# pcb_telemetria.net
KiCad netlist of a schematic drawn in EAGLE
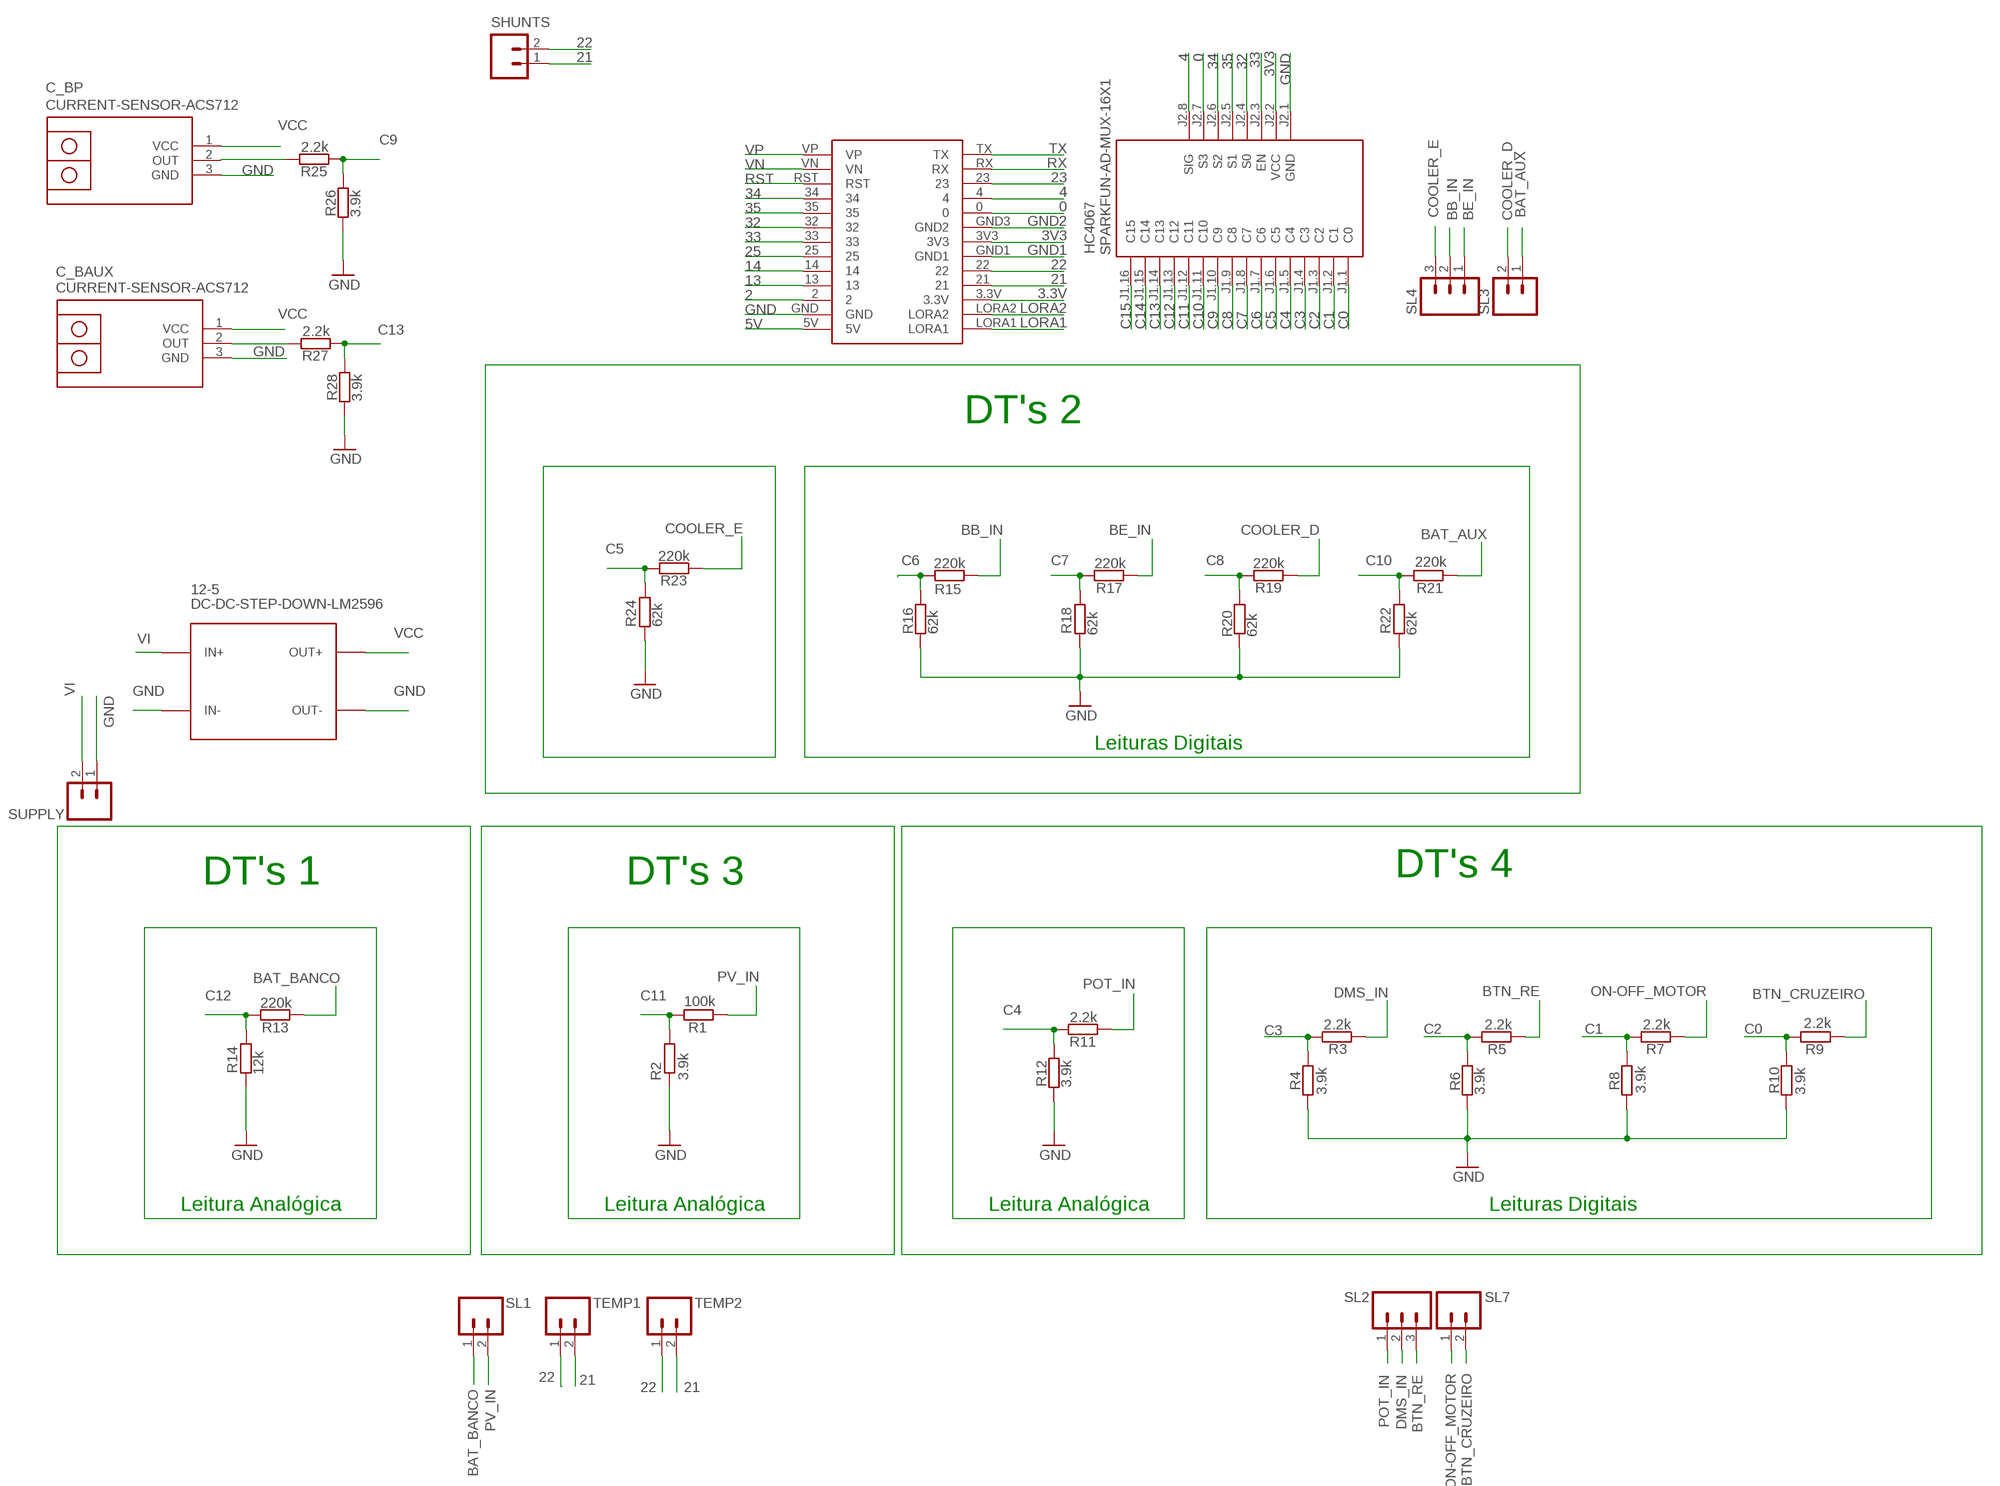
[diagram p0: schematic, sheet 1]

(export (version "E")
  (design (tool "Eeschema 10.0.6"))
  (components
    (comp (ref "12-5")
      (value "DC-DC-STEP-DOWN-LM2596")
      (footprint "eagle-import:DC-DC-STEP-DOWN-LM2596")
      (libsource (lib "eagle-import") (part "DC-DC-STEP-DOWN-LM2596"))
    )
    (comp (ref "C_BAUX")
      (value "CURRENT-SENSOR-ACS712")
      (footprint "eagle-import:CURRENT-SENSOR-ACS712")
      (libsource (lib "eagle-import") (part "CURRENT-SENSOR-ACS712"))
    )
    (comp (ref "C_BP")
      (value "CURRENT-SENSOR-ACS712")
      (footprint "eagle-import:CURRENT-SENSOR-ACS712")
      (libsource (lib "eagle-import") (part "CURRENT-SENSOR-ACS712"))
    )
    (comp (ref "HC4067")
      (value "SPARKFUN-AD-MUX-16X1")
      (footprint "eagle-import:SPARKFUN-AD-MUX-16X1")
      (libsource (lib "eagle-import") (part "SPARKFUN-AD-MUX-16X1"))
    )
    (comp (ref "R1")
      (value "100k")
      (footprint "eagle-import:0204_7")
      (libsource (lib "eagle-import") (part "R-EU_0204/7"))
    )
    (comp (ref "R2")
      (value "3.9k")
      (footprint "eagle-import:0204_7")
      (libsource (lib "eagle-import") (part "R-EU_0204/7"))
    )
    (comp (ref "R3")
      (value "2.2k")
      (footprint "eagle-import:0204_7")
      (libsource (lib "eagle-import") (part "R-EU_0204/7"))
    )
    (comp (ref "R4")
      (value "3.9k")
      (footprint "eagle-import:0204_7")
      (libsource (lib "eagle-import") (part "R-EU_0204/7"))
    )
    (comp (ref "R5")
      (value "2.2k")
      (footprint "eagle-import:0204_7")
      (libsource (lib "eagle-import") (part "R-EU_0204/7"))
    )
    (comp (ref "R6")
      (value "3.9k")
      (footprint "eagle-import:0204_7")
      (libsource (lib "eagle-import") (part "R-EU_0204/7"))
    )
    (comp (ref "R7")
      (value "2.2k")
      (footprint "eagle-import:0204_7")
      (libsource (lib "eagle-import") (part "R-EU_0204/7"))
    )
    (comp (ref "R8")
      (value "3.9k")
      (footprint "eagle-import:0204_7")
      (libsource (lib "eagle-import") (part "R-EU_0204/7"))
    )
    (comp (ref "R9")
      (value "2.2k")
      (footprint "eagle-import:0204_7")
      (libsource (lib "eagle-import") (part "R-EU_0204/7"))
    )
    (comp (ref "R10")
      (value "3.9k")
      (footprint "eagle-import:0204_7")
      (libsource (lib "eagle-import") (part "R-EU_0204/7"))
    )
    (comp (ref "R11")
      (value "2.2k")
      (footprint "eagle-import:0204_7")
      (libsource (lib "eagle-import") (part "R-EU_0204/7"))
    )
    (comp (ref "R12")
      (value "3.9k")
      (footprint "eagle-import:0204_7")
      (libsource (lib "eagle-import") (part "R-EU_0204/7"))
    )
    (comp (ref "R13")
      (value "220k")
      (footprint "eagle-import:0204_7")
      (libsource (lib "eagle-import") (part "R-EU_0204/7"))
    )
    (comp (ref "R14")
      (value "12k")
      (footprint "eagle-import:0204_7")
      (libsource (lib "eagle-import") (part "R-EU_0204/7"))
    )
    (comp (ref "R15")
      (value "220k")
      (footprint "eagle-import:0204_7")
      (libsource (lib "eagle-import") (part "R-EU_0204/7"))
    )
    (comp (ref "R16")
      (value "62k")
      (footprint "eagle-import:0204_7")
      (libsource (lib "eagle-import") (part "R-EU_0204/7"))
    )
    (comp (ref "R17")
      (value "220k")
      (footprint "eagle-import:0204_7")
      (libsource (lib "eagle-import") (part "R-EU_0204/7"))
    )
    (comp (ref "R18")
      (value "62k")
      (footprint "eagle-import:0204_7")
      (libsource (lib "eagle-import") (part "R-EU_0204/7"))
    )
    (comp (ref "R19")
      (value "220k")
      (footprint "eagle-import:0204_7")
      (libsource (lib "eagle-import") (part "R-EU_0204/7"))
    )
    (comp (ref "R20")
      (value "62k")
      (footprint "eagle-import:0204_7")
      (libsource (lib "eagle-import") (part "R-EU_0204/7"))
    )
    (comp (ref "R21")
      (value "220k")
      (footprint "eagle-import:0204_7")
      (libsource (lib "eagle-import") (part "R-EU_0204/7"))
    )
    (comp (ref "R22")
      (value "62k")
      (footprint "eagle-import:0204_7")
      (libsource (lib "eagle-import") (part "R-EU_0204/7"))
    )
    (comp (ref "R23")
      (value "220k")
      (footprint "eagle-import:0204_7")
      (libsource (lib "eagle-import") (part "R-EU_0204/7"))
    )
    (comp (ref "R24")
      (value "62k")
      (footprint "eagle-import:0204_7")
      (libsource (lib "eagle-import") (part "R-EU_0204/7"))
    )
    (comp (ref "R25")
      (value "2.2k")
      (footprint "eagle-import:0204_7")
      (libsource (lib "eagle-import") (part "R-EU_0204/7"))
    )
    (comp (ref "R26")
      (value "3.9k")
      (footprint "eagle-import:0204_7")
      (libsource (lib "eagle-import") (part "R-EU_0204/7"))
    )
    (comp (ref "R27")
      (value "2.2k")
      (footprint "eagle-import:0204_7")
      (libsource (lib "eagle-import") (part "R-EU_0204/7"))
    )
    (comp (ref "R28")
      (value "3.9k")
      (footprint "eagle-import:0204_7")
      (libsource (lib "eagle-import") (part "R-EU_0204/7"))
    )
    (comp (ref "SHUNTS")
      (value "M02")
      (footprint "eagle-import:02P")
      (libsource (lib "eagle-import") (part "M02"))
    )
    (comp (ref "SL1")
      (value "M02")
      (footprint "eagle-import:02P")
      (libsource (lib "eagle-import") (part "M02"))
    )
    (comp (ref "SL2")
      (value "M03")
      (footprint "eagle-import:03P")
      (libsource (lib "eagle-import") (part "M03"))
    )
    (comp (ref "SL3")
      (value "M02")
      (footprint "eagle-import:02P")
      (libsource (lib "eagle-import") (part "M02"))
    )
    (comp (ref "SL4")
      (value "M03")
      (footprint "eagle-import:03P")
      (libsource (lib "eagle-import") (part "M03"))
    )
    (comp (ref "SL7")
      (value "M02")
      (footprint "eagle-import:02P")
      (libsource (lib "eagle-import") (part "M02"))
    )
    (comp (ref "SUPPLY")
      (value "M02")
      (footprint "eagle-import:02P")
      (libsource (lib "eagle-import") (part "M02"))
    )
    (comp (ref "TEMP1")
      (value "M02")
      (footprint "eagle-import:02P")
      (libsource (lib "eagle-import") (part "M02"))
    )
    (comp (ref "TEMP2")
      (value "M02")
      (footprint "eagle-import:02P")
      (libsource (lib "eagle-import") (part "M02"))
    )
    (comp (ref "U$1")
      (value "TTGOBEAM")
      (footprint "eagle-import:TTGOBEAM")
      (libsource (lib "eagle-import") (part "TTGOBEAM"))
    )
  )
  (nets
    (net (code "1") (name "/0") (class "Default")
      (node (ref "HC4067") (pin "J2.7") (pinfunction "S3_J2.7") (pintype "bidirectional"))
      (node (ref "U$1") (pin "0") (pinfunction "0_0") (pintype "bidirectional"))
    )
    (net (code "2") (name "/2") (class "Default")
      (node (ref "U$1") (pin "2") (pinfunction "2_2") (pintype "bidirectional"))
    )
    (net (code "3") (name "/3.3V") (class "Default")
      (node (ref "U$1") (pin "3.3V") (pinfunction "3.3V_3.3V") (pintype "bidirectional"))
    )
    (net (code "4") (name "/3V3") (class "Default")
      (node (ref "HC4067") (pin "J2.2") (pinfunction "VCC_J2.2") (pintype "power_in"))
      (node (ref "U$1") (pin "3V3") (pinfunction "3V3_3V3") (pintype "bidirectional"))
    )
    (net (code "5") (name "/4") (class "Default")
      (node (ref "HC4067") (pin "J2.8") (pinfunction "SIG_J2.8") (pintype "bidirectional"))
      (node (ref "U$1") (pin "4") (pinfunction "4_4") (pintype "bidirectional"))
    )
    (net (code "6") (name "/5V") (class "Default")
      (node (ref "U$1") (pin "5V") (pinfunction "5V_5V") (pintype "bidirectional"))
    )
    (net (code "7") (name "/13") (class "Default")
      (node (ref "U$1") (pin "13") (pinfunction "13_13") (pintype "bidirectional"))
    )
    (net (code "8") (name "/14") (class "Default")
      (node (ref "U$1") (pin "14") (pinfunction "14_14") (pintype "bidirectional"))
    )
    (net (code "9") (name "/21") (class "Default")
      (node (ref "SHUNTS") (pin "1") (pinfunction "1_1") (pintype "passive"))
      (node (ref "TEMP1") (pin "2") (pinfunction "2_2") (pintype "passive"))
      (node (ref "TEMP2") (pin "2") (pinfunction "2_2") (pintype "passive"))
      (node (ref "U$1") (pin "21") (pinfunction "21_21") (pintype "bidirectional"))
    )
    (net (code "10") (name "/22") (class "Default")
      (node (ref "SHUNTS") (pin "2") (pinfunction "2_2") (pintype "passive"))
      (node (ref "TEMP1") (pin "1") (pinfunction "1_1") (pintype "passive"))
      (node (ref "TEMP2") (pin "1") (pinfunction "1_1") (pintype "passive"))
      (node (ref "U$1") (pin "22") (pinfunction "22_22") (pintype "bidirectional"))
    )
    (net (code "11") (name "/23") (class "Default")
      (node (ref "U$1") (pin "23") (pinfunction "23_23") (pintype "bidirectional"))
    )
    (net (code "12") (name "/25") (class "Default")
      (node (ref "U$1") (pin "25") (pinfunction "25_25") (pintype "bidirectional"))
    )
    (net (code "13") (name "/32") (class "Default")
      (node (ref "HC4067") (pin "J2.4") (pinfunction "S0_J2.4") (pintype "bidirectional"))
      (node (ref "U$1") (pin "32") (pinfunction "32_32") (pintype "bidirectional"))
    )
    (net (code "14") (name "/33") (class "Default")
      (node (ref "HC4067") (pin "J2.3") (pinfunction "EN_J2.3") (pintype "input"))
      (node (ref "U$1") (pin "33") (pinfunction "33_33") (pintype "bidirectional"))
    )
    (net (code "15") (name "/34") (class "Default")
      (node (ref "HC4067") (pin "J2.6") (pinfunction "S2_J2.6") (pintype "bidirectional"))
      (node (ref "U$1") (pin "34") (pinfunction "34_34") (pintype "bidirectional"))
    )
    (net (code "16") (name "/35") (class "Default")
      (node (ref "HC4067") (pin "J2.5") (pinfunction "S1_J2.5") (pintype "bidirectional"))
      (node (ref "U$1") (pin "35") (pinfunction "35_35") (pintype "bidirectional"))
    )
    (net (code "17") (name "/BAT_AUX") (class "Default")
      (node (ref "R21") (pin "2") (pinfunction "2_2") (pintype "passive"))
      (node (ref "SL3") (pin "1") (pinfunction "1_1") (pintype "passive"))
    )
    (net (code "18") (name "/BAT_BANCO") (class "Default")
      (node (ref "R13") (pin "2") (pinfunction "2_2") (pintype "passive"))
      (node (ref "SL1") (pin "1") (pinfunction "1_1") (pintype "passive"))
    )
    (net (code "19") (name "/BB_IN") (class "Default")
      (node (ref "R15") (pin "1") (pinfunction "1_1") (pintype "passive"))
      (node (ref "SL4") (pin "2") (pinfunction "2_2") (pintype "passive"))
    )
    (net (code "20") (name "/BE_IN") (class "Default")
      (node (ref "R17") (pin "2") (pinfunction "2_2") (pintype "passive"))
      (node (ref "SL4") (pin "1") (pinfunction "1_1") (pintype "passive"))
    )
    (net (code "21") (name "/BTN_CRUZEIRO") (class "Default")
      (node (ref "R9") (pin "2") (pinfunction "2_2") (pintype "passive"))
      (node (ref "SL7") (pin "2") (pinfunction "2_2") (pintype "passive"))
    )
    (net (code "22") (name "/BTN_RE") (class "Default")
      (node (ref "R5") (pin "2") (pinfunction "2_2") (pintype "passive"))
      (node (ref "SL2") (pin "3") (pinfunction "3_3") (pintype "passive"))
    )
    (net (code "23") (name "/C0") (class "Default")
      (node (ref "HC4067") (pin "J1.1") (pinfunction "C0_J1.1") (pintype "bidirectional"))
      (node (ref "R10") (pin "2") (pinfunction "2_2") (pintype "passive"))
      (node (ref "R9") (pin "1") (pinfunction "1_1") (pintype "passive"))
    )
    (net (code "24") (name "/C1") (class "Default")
      (node (ref "HC4067") (pin "J1.2") (pinfunction "C1_J1.2") (pintype "bidirectional"))
      (node (ref "R7") (pin "2") (pinfunction "2_2") (pintype "passive"))
      (node (ref "R8") (pin "1") (pinfunction "1_1") (pintype "passive"))
    )
    (net (code "25") (name "/C2") (class "Default")
      (node (ref "HC4067") (pin "J1.3") (pinfunction "C2_J1.3") (pintype "bidirectional"))
      (node (ref "R5") (pin "1") (pinfunction "1_1") (pintype "passive"))
      (node (ref "R6") (pin "2") (pinfunction "2_2") (pintype "passive"))
    )
    (net (code "26") (name "/C3") (class "Default")
      (node (ref "HC4067") (pin "J1.4") (pinfunction "C3_J1.4") (pintype "bidirectional"))
      (node (ref "R3") (pin "2") (pinfunction "2_2") (pintype "passive"))
      (node (ref "R4") (pin "1") (pinfunction "1_1") (pintype "passive"))
    )
    (net (code "27") (name "/C4") (class "Default")
      (node (ref "HC4067") (pin "J1.5") (pinfunction "C4_J1.5") (pintype "bidirectional"))
      (node (ref "R11") (pin "2") (pinfunction "2_2") (pintype "passive"))
      (node (ref "R12") (pin "1") (pinfunction "1_1") (pintype "passive"))
    )
    (net (code "28") (name "/C5") (class "Default")
      (node (ref "HC4067") (pin "J1.6") (pinfunction "C5_J1.6") (pintype "bidirectional"))
      (node (ref "R23") (pin "2") (pinfunction "2_2") (pintype "passive"))
      (node (ref "R24") (pin "1") (pinfunction "1_1") (pintype "passive"))
    )
    (net (code "29") (name "/C6") (class "Default")
      (node (ref "HC4067") (pin "J1.7") (pinfunction "C6_J1.7") (pintype "bidirectional"))
      (node (ref "R15") (pin "2") (pinfunction "2_2") (pintype "passive"))
      (node (ref "R16") (pin "1") (pinfunction "1_1") (pintype "passive"))
    )
    (net (code "30") (name "/C7") (class "Default")
      (node (ref "HC4067") (pin "J1.8") (pinfunction "C7_J1.8") (pintype "bidirectional"))
      (node (ref "R17") (pin "1") (pinfunction "1_1") (pintype "passive"))
      (node (ref "R18") (pin "2") (pinfunction "2_2") (pintype "passive"))
    )
    (net (code "31") (name "/C8") (class "Default")
      (node (ref "HC4067") (pin "J1.9") (pinfunction "C8_J1.9") (pintype "bidirectional"))
      (node (ref "R19") (pin "2") (pinfunction "2_2") (pintype "passive"))
      (node (ref "R20") (pin "1") (pinfunction "1_1") (pintype "passive"))
    )
    (net (code "32") (name "/C9") (class "Default")
      (node (ref "HC4067") (pin "J1.10") (pinfunction "C9_J1.10") (pintype "bidirectional"))
      (node (ref "R25") (pin "1") (pinfunction "1_1") (pintype "passive"))
      (node (ref "R26") (pin "1") (pinfunction "1_1") (pintype "passive"))
    )
    (net (code "33") (name "/C10") (class "Default")
      (node (ref "HC4067") (pin "J1.11") (pinfunction "C10_J1.11") (pintype "bidirectional"))
      (node (ref "R21") (pin "1") (pinfunction "1_1") (pintype "passive"))
      (node (ref "R22") (pin "2") (pinfunction "2_2") (pintype "passive"))
    )
    (net (code "34") (name "/C11") (class "Default")
      (node (ref "HC4067") (pin "J1.12") (pinfunction "C11_J1.12") (pintype "bidirectional"))
      (node (ref "R1") (pin "1") (pinfunction "1_1") (pintype "passive"))
      (node (ref "R2") (pin "2") (pinfunction "2_2") (pintype "passive"))
    )
    (net (code "35") (name "/C12") (class "Default")
      (node (ref "HC4067") (pin "J1.13") (pinfunction "C12_J1.13") (pintype "bidirectional"))
      (node (ref "R13") (pin "1") (pinfunction "1_1") (pintype "passive"))
      (node (ref "R14") (pin "2") (pinfunction "2_2") (pintype "passive"))
    )
    (net (code "36") (name "/C13") (class "Default")
      (node (ref "HC4067") (pin "J1.14") (pinfunction "C13_J1.14") (pintype "bidirectional"))
      (node (ref "R27") (pin "1") (pinfunction "1_1") (pintype "passive"))
      (node (ref "R28") (pin "1") (pinfunction "1_1") (pintype "passive"))
    )
    (net (code "37") (name "/C14") (class "Default")
      (node (ref "HC4067") (pin "J1.15") (pinfunction "C14_J1.15") (pintype "bidirectional"))
    )
    (net (code "38") (name "/C15") (class "Default")
      (node (ref "HC4067") (pin "J1.16") (pinfunction "C15_J1.16") (pintype "bidirectional"))
    )
    (net (code "39") (name "/COOLER_D") (class "Default")
      (node (ref "R19") (pin "1") (pinfunction "1_1") (pintype "passive"))
      (node (ref "SL3") (pin "2") (pinfunction "2_2") (pintype "passive"))
    )
    (net (code "40") (name "/COOLER_E") (class "Default")
      (node (ref "R23") (pin "1") (pinfunction "1_1") (pintype "passive"))
      (node (ref "SL4") (pin "3") (pinfunction "3_3") (pintype "passive"))
    )
    (net (code "41") (name "/DMS_IN") (class "Default")
      (node (ref "R3") (pin "1") (pinfunction "1_1") (pintype "passive"))
      (node (ref "SL2") (pin "2") (pinfunction "2_2") (pintype "passive"))
    )
    (net (code "42") (name "/GND1") (class "Default")
      (node (ref "U$1") (pin "GND1") (pinfunction "GND1_GND1") (pintype "bidirectional"))
    )
    (net (code "43") (name "/GND2") (class "Default")
      (node (ref "U$1") (pin "GND3") (pinfunction "GND2_GND3") (pintype "bidirectional"))
    )
    (net (code "44") (name "/LORA1") (class "Default")
      (node (ref "U$1") (pin "LORA1") (pinfunction "LORA1_LORA1") (pintype "bidirectional"))
    )
    (net (code "45") (name "/LORA2") (class "Default")
      (node (ref "U$1") (pin "LORA2") (pinfunction "LORA2_LORA2") (pintype "bidirectional"))
    )
    (net (code "46") (name "/ON-OFF_MOTOR") (class "Default")
      (node (ref "R7") (pin "1") (pinfunction "1_1") (pintype "passive"))
      (node (ref "SL7") (pin "1") (pinfunction "1_1") (pintype "passive"))
    )
    (net (code "47") (name "/POT_IN") (class "Default")
      (node (ref "R11") (pin "1") (pinfunction "1_1") (pintype "passive"))
      (node (ref "SL2") (pin "1") (pinfunction "1_1") (pintype "passive"))
    )
    (net (code "48") (name "/PV_IN") (class "Default")
      (node (ref "R1") (pin "2") (pinfunction "2_2") (pintype "passive"))
      (node (ref "SL1") (pin "2") (pinfunction "2_2") (pintype "passive"))
    )
    (net (code "49") (name "/RST") (class "Default")
      (node (ref "U$1") (pin "RST") (pinfunction "RST_RST") (pintype "bidirectional"))
    )
    (net (code "50") (name "/RX") (class "Default")
      (node (ref "U$1") (pin "RX") (pinfunction "RX_RX") (pintype "bidirectional"))
    )
    (net (code "51") (name "/TX") (class "Default")
      (node (ref "U$1") (pin "TX") (pinfunction "TX_TX") (pintype "bidirectional"))
    )
    (net (code "52") (name "/VCC") (class "Default")
      (node (ref "12-5") (pin "OUT+") (pinfunction "OUT+_OUT+") (pintype "bidirectional"))
      (node (ref "C_BAUX") (pin "1") (pinfunction "VCC_1") (pintype "power_in"))
      (node (ref "C_BP") (pin "1") (pinfunction "VCC_1") (pintype "power_in"))
    )
    (net (code "53") (name "/VI") (class "Default")
      (node (ref "12-5") (pin "IN+") (pinfunction "IN+_IN+") (pintype "bidirectional"))
      (node (ref "SUPPLY") (pin "2") (pinfunction "2_2") (pintype "passive"))
    )
    (net (code "54") (name "/VN") (class "Default")
      (node (ref "U$1") (pin "VN") (pinfunction "VN_VN") (pintype "bidirectional"))
    )
    (net (code "55") (name "/VP") (class "Default")
      (node (ref "U$1") (pin "VP") (pinfunction "VP_VP") (pintype "bidirectional"))
    )
    (net (code "56") (name "GND") (class "Default")
      (node (ref "12-5") (pin "IN-") (pinfunction "IN-_IN-") (pintype "bidirectional"))
      (node (ref "12-5") (pin "OUT-") (pinfunction "OUT-_OUT-") (pintype "bidirectional"))
      (node (ref "C_BAUX") (pin "3") (pinfunction "GND_3") (pintype "power_in"))
      (node (ref "C_BP") (pin "3") (pinfunction "GND_3") (pintype "power_in"))
      (node (ref "HC4067") (pin "J2.1") (pinfunction "GND_J2.1") (pintype "power_in"))
      (node (ref "R10") (pin "1") (pinfunction "1_1") (pintype "passive"))
      (node (ref "R12") (pin "2") (pinfunction "2_2") (pintype "passive"))
      (node (ref "R14") (pin "1") (pinfunction "1_1") (pintype "passive"))
      (node (ref "R16") (pin "2") (pinfunction "2_2") (pintype "passive"))
      (node (ref "R18") (pin "1") (pinfunction "1_1") (pintype "passive"))
      (node (ref "R2") (pin "1") (pinfunction "1_1") (pintype "passive"))
      (node (ref "R20") (pin "2") (pinfunction "2_2") (pintype "passive"))
      (node (ref "R22") (pin "1") (pinfunction "1_1") (pintype "passive"))
      (node (ref "R24") (pin "2") (pinfunction "2_2") (pintype "passive"))
      (node (ref "R26") (pin "2") (pinfunction "2_2") (pintype "passive"))
      (node (ref "R28") (pin "2") (pinfunction "2_2") (pintype "passive"))
      (node (ref "R4") (pin "2") (pinfunction "2_2") (pintype "passive"))
      (node (ref "R6") (pin "1") (pinfunction "1_1") (pintype "passive"))
      (node (ref "R8") (pin "2") (pinfunction "2_2") (pintype "passive"))
      (node (ref "SUPPLY") (pin "1") (pinfunction "1_1") (pintype "passive"))
      (node (ref "U$1") (pin "GND") (pinfunction "GND_GND") (pintype "bidirectional"))
    )
    (net (code "57") (name "Net-(C_BAUX-OUT)") (class "Default")
      (node (ref "C_BAUX") (pin "2") (pinfunction "OUT_2") (pintype "output"))
      (node (ref "R27") (pin "2") (pinfunction "2_2") (pintype "passive"))
    )
    (net (code "58") (name "Net-(C_BP-OUT)") (class "Default")
      (node (ref "C_BP") (pin "2") (pinfunction "OUT_2") (pintype "output"))
      (node (ref "R25") (pin "2") (pinfunction "2_2") (pintype "passive"))
    )
  )
)
